# RHC12-BTA.net
KiCad netlist of a schematic drawn in EAGLE
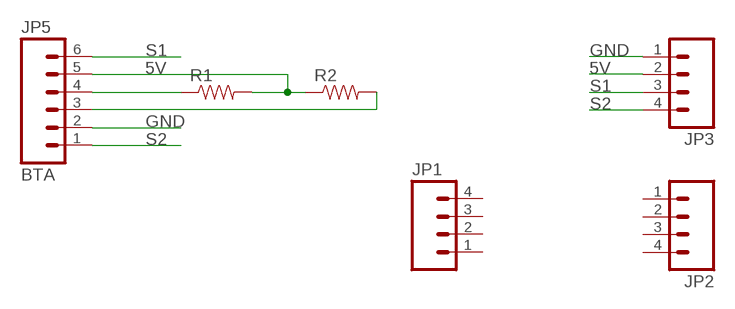
[diagram p0: schematic, sheet 1]

(export (version "E")
  (design (tool "Eeschema 10.0.6"))
  (components
    (comp (ref "JP1")
      (value "M04NO_SILK_ALL_ROUND")
      (footprint "eagle-import:1X04_NO_SILK_ALL_ROUND")
      (libsource (lib "eagle-import") (part "M04NO_SILK_ALL_ROUND"))
    )
    (comp (ref "JP2")
      (value "M04NO_SILK_ALL_ROUND")
      (footprint "eagle-import:1X04_NO_SILK_ALL_ROUND")
      (libsource (lib "eagle-import") (part "M04NO_SILK_ALL_ROUND"))
    )
    (comp (ref "JP3")
      (value "M04NO_SILK_ALL_ROUND")
      (footprint "eagle-import:1X04_NO_SILK_ALL_ROUND")
      (libsource (lib "eagle-import") (part "M04NO_SILK_ALL_ROUND"))
    )
    (comp (ref "JP5")
      (value "BTA")
      (footprint "eagle-import:BTA")
      (libsource (lib "eagle-import") (part "M06VERNIER-ANALOG"))
    )
    (comp (ref "R1")
      (value "RESISTORPTH-1/4W")
      (footprint "eagle-import:AXIAL-0.4")
      (libsource (lib "eagle-import") (part "RESISTORPTH-1/4W"))
    )
    (comp (ref "R2")
      (value "RESISTORPTH-1/4W")
      (footprint "eagle-import:AXIAL-0.4")
      (libsource (lib "eagle-import") (part "RESISTORPTH-1/4W"))
    )
  )
  (nets
    (net (code "1") (name "/5V") (class "Default")
      (node (ref "JP3") (pin "2") (pinfunction "2_2") (pintype "passive"))
      (node (ref "JP5") (pin "5") (pinfunction "5_5") (pintype "passive"))
      (node (ref "R1") (pin "P$2") (pinfunction "2_P$2") (pintype "passive"))
      (node (ref "R2") (pin "P$1") (pinfunction "1_P$1") (pintype "passive"))
    )
    (net (code "2") (name "/GND") (class "Default")
      (node (ref "JP3") (pin "1") (pinfunction "1_1") (pintype "passive"))
      (node (ref "JP5") (pin "2") (pinfunction "2_2") (pintype "passive"))
    )
    (net (code "3") (name "/S1") (class "Default")
      (node (ref "JP3") (pin "3") (pinfunction "3_3") (pintype "passive"))
      (node (ref "JP5") (pin "6") (pinfunction "6_6") (pintype "passive"))
    )
    (net (code "4") (name "/S2") (class "Default")
      (node (ref "JP3") (pin "4") (pinfunction "4_4") (pintype "passive"))
      (node (ref "JP5") (pin "1") (pinfunction "1_1") (pintype "passive"))
    )
    (net (code "5") (name "Net-(R1-1)") (class "Default")
      (node (ref "JP5") (pin "4") (pinfunction "4_4") (pintype "passive"))
      (node (ref "R1") (pin "P$1") (pinfunction "1_P$1") (pintype "passive"))
    )
    (net (code "6") (name "Net-(R2-2)") (class "Default")
      (node (ref "JP5") (pin "3") (pinfunction "3_3") (pintype "passive"))
      (node (ref "R2") (pin "P$2") (pinfunction "2_P$2") (pintype "passive"))
    )
    (net (code "7") (name "unconnected-(JP1-Pad1)") (class "Default")
      (node (ref "JP1") (pin "1") (pinfunction "1_1") (pintype "passive"))
    )
    (net (code "8") (name "unconnected-(JP1-Pad2)") (class "Default")
      (node (ref "JP1") (pin "2") (pinfunction "2_2") (pintype "passive"))
    )
    (net (code "9") (name "unconnected-(JP1-Pad3)") (class "Default")
      (node (ref "JP1") (pin "3") (pinfunction "3_3") (pintype "passive"))
    )
    (net (code "10") (name "unconnected-(JP1-Pad4)") (class "Default")
      (node (ref "JP1") (pin "4") (pinfunction "4_4") (pintype "passive"))
    )
    (net (code "11") (name "unconnected-(JP2-Pad1)") (class "Default")
      (node (ref "JP2") (pin "1") (pinfunction "1_1") (pintype "passive"))
    )
    (net (code "12") (name "unconnected-(JP2-Pad2)") (class "Default")
      (node (ref "JP2") (pin "2") (pinfunction "2_2") (pintype "passive"))
    )
    (net (code "13") (name "unconnected-(JP2-Pad3)") (class "Default")
      (node (ref "JP2") (pin "3") (pinfunction "3_3") (pintype "passive"))
    )
    (net (code "14") (name "unconnected-(JP2-Pad4)") (class "Default")
      (node (ref "JP2") (pin "4") (pinfunction "4_4") (pintype "passive"))
    )
  )
)
